# CHILD_BOARD.net
KiCad netlist of a schematic drawn in Altium Designer
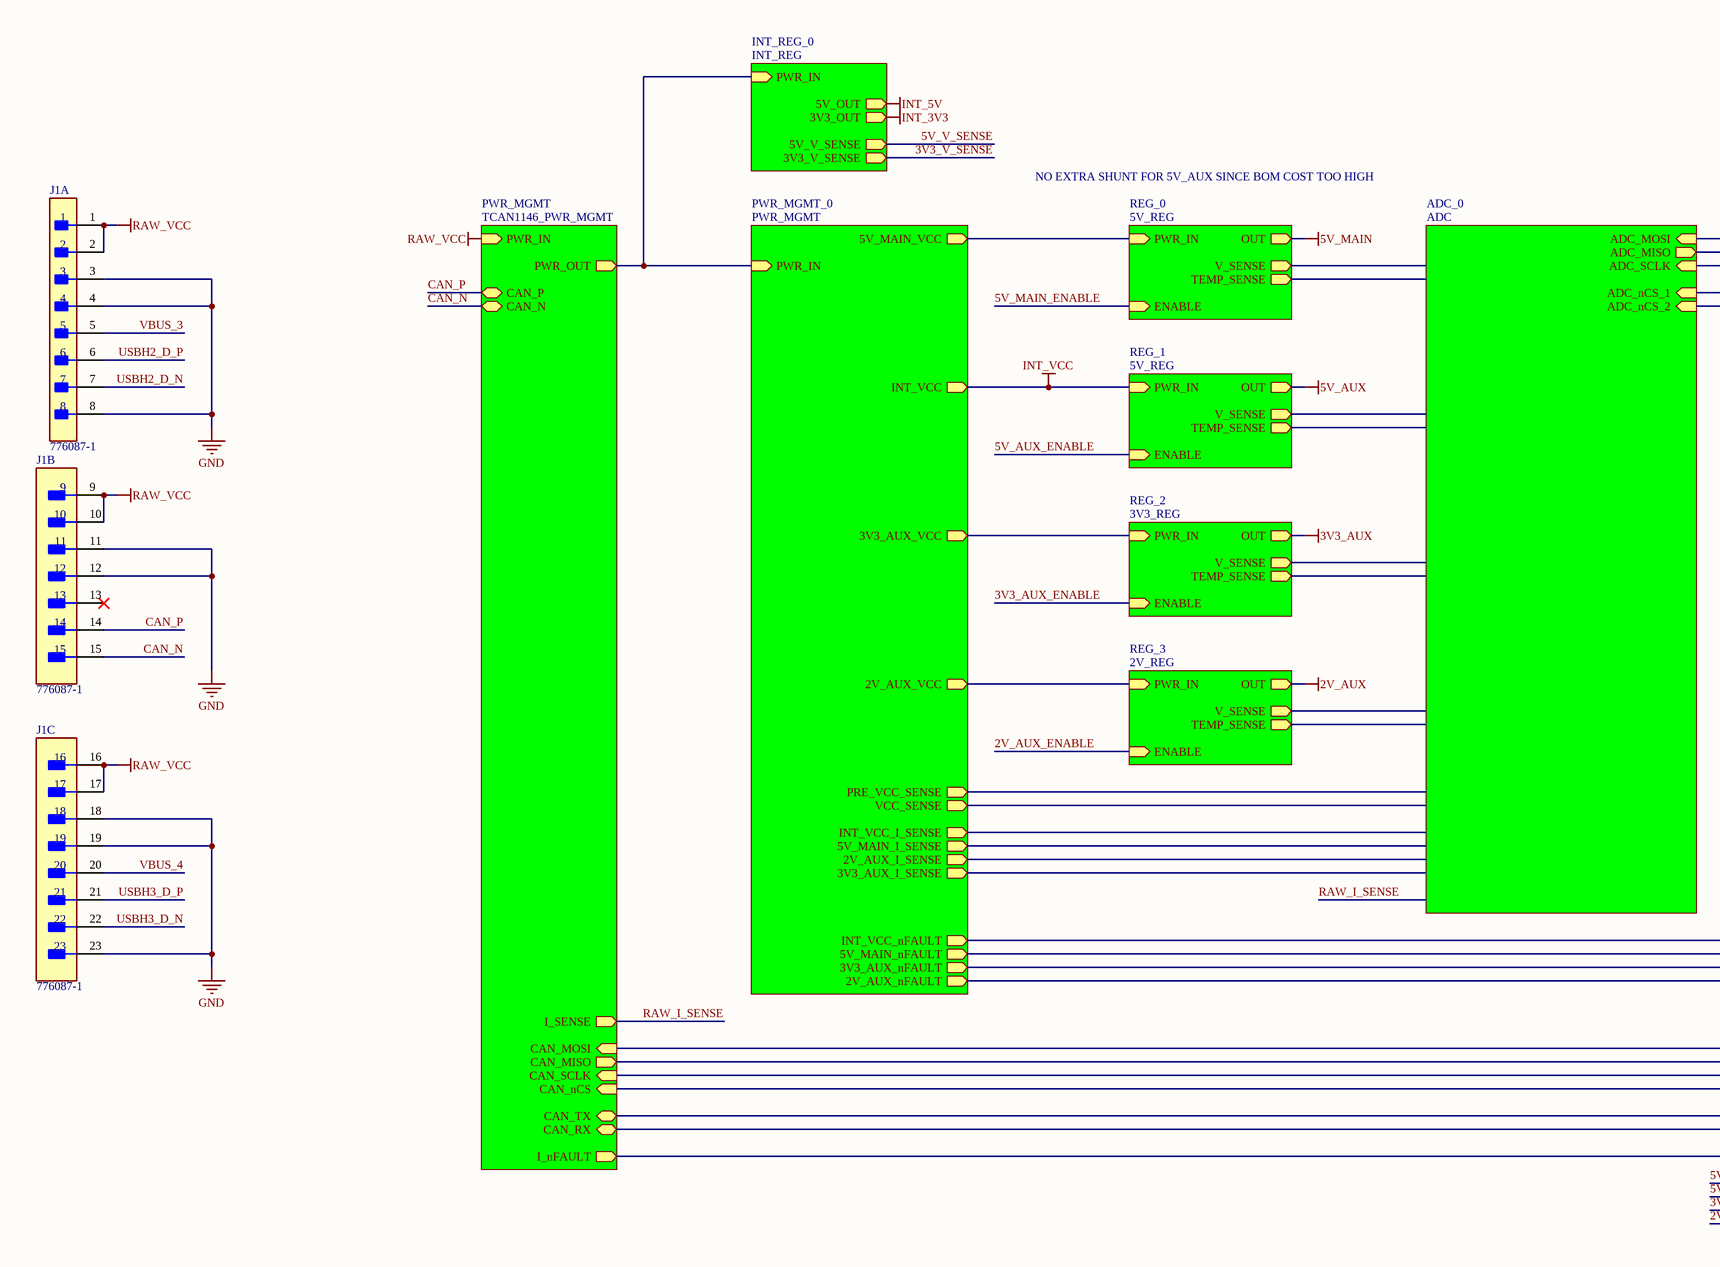
[diagram p0: CHILD_BOARD.SchDoc, left]
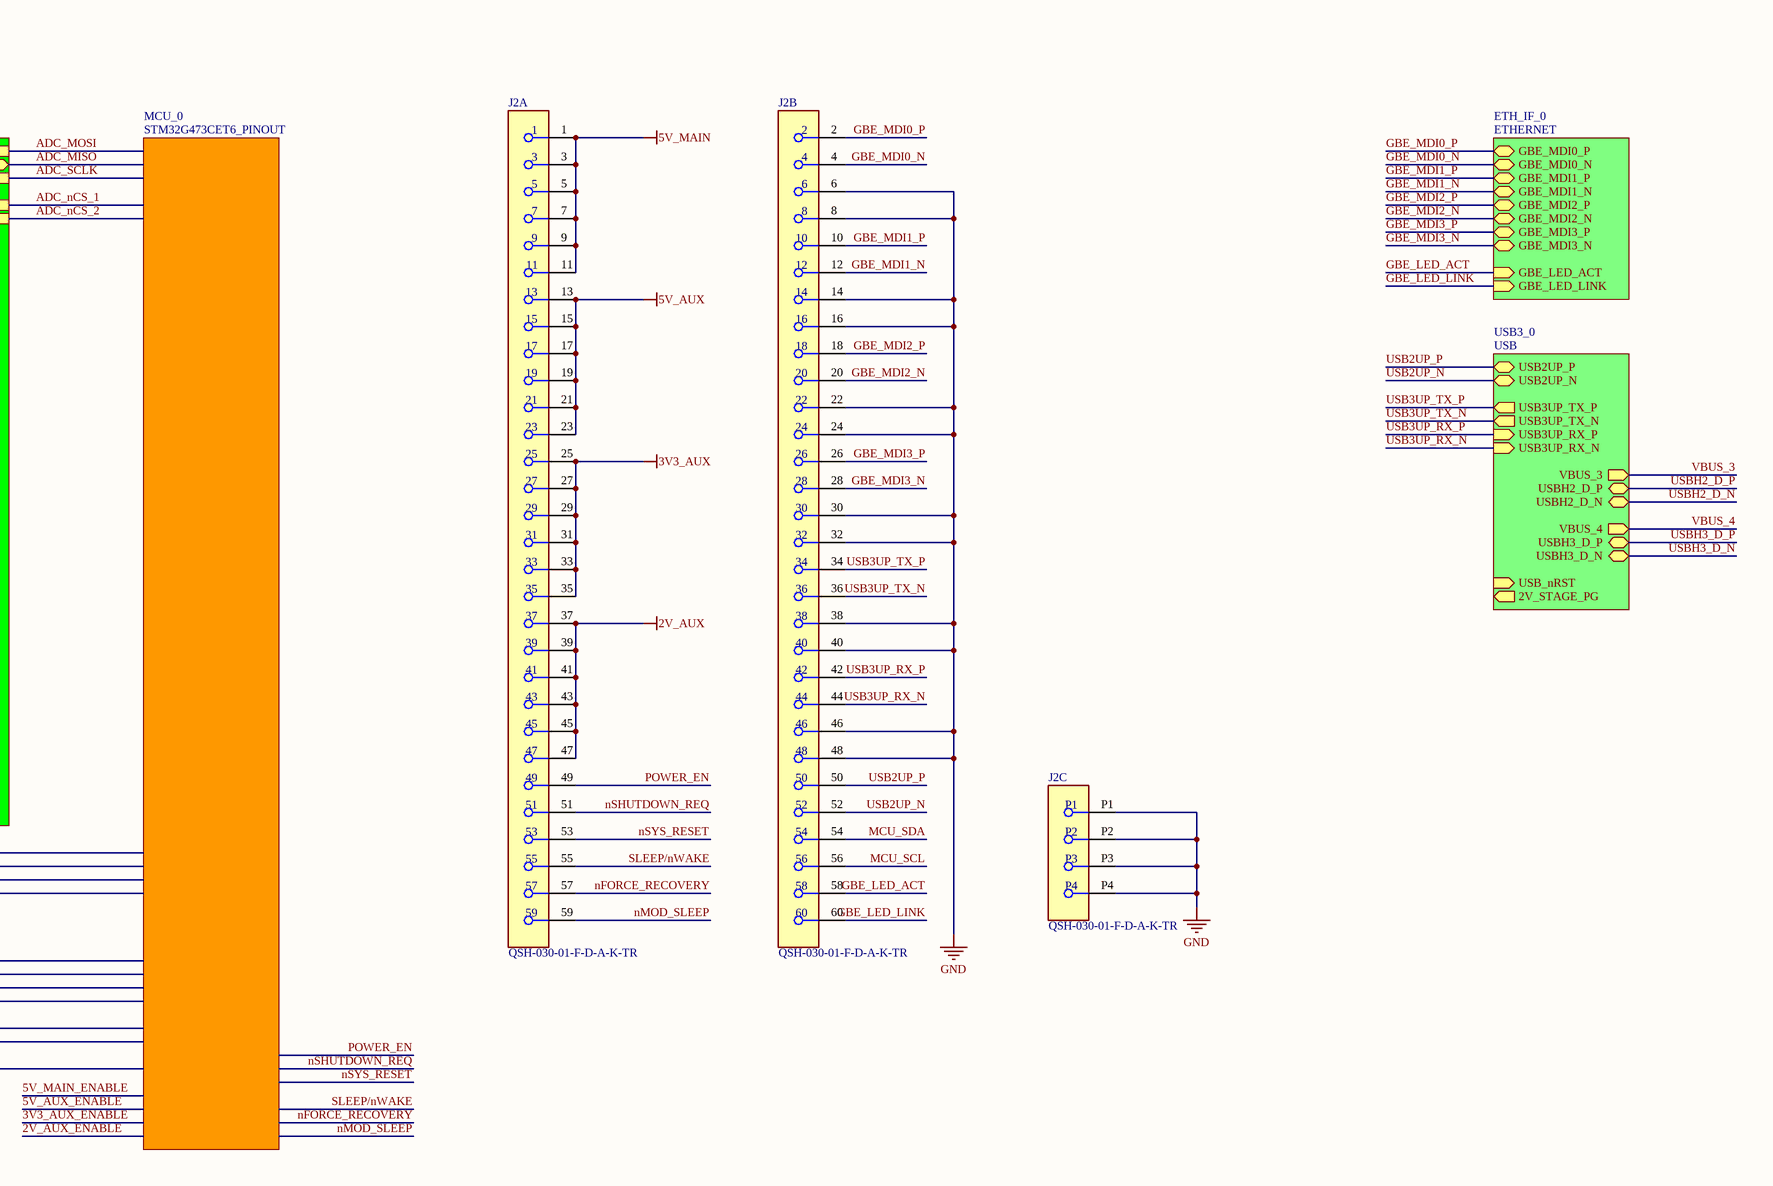
[diagram p1: CHILD_BOARD.SchDoc, right]

(export (version "E")
  (design (tool "Eeschema 10.0.6"))
  (components
    (comp (ref "J1")
      (value "776087-1")
      (footprint "FP-776087-1-MFG")
      (description "CONN HEADER R/A 23POS 4MM")
      (libsource (lib "Altium Content Vault") (part "1cdbe6524175775e54446a79a4f0ed8"))
    )
    (comp (ref "J2")
      (value "QSH-030-01-F-D-A-K-TR")
      (footprint "FP-QSH-030-01-F-D-A-K-TR-MFG")
      (description "CONN RCPT 60POS SMD GOLD")
      (libsource (lib "Altium Content Vault") (part "48abaac3d53574362e26c425c264dad"))
    )
  )
  (nets
    (net (code "24") (name "/CAN_N") (class "Default")
      (node (ref "J1") (pin "15") (pinfunction "15_15") (pintype "passive"))
    )
    (net (code "25") (name "/CAN_P") (class "Default")
      (node (ref "J1") (pin "14") (pinfunction "14_14") (pintype "passive"))
    )
    (net (code "30") (name "/GBE_LED_ACT") (class "Default")
      (node (ref "J2") (pin "58") (pinfunction "58_58") (pintype "passive"))
    )
    (net (code "31") (name "/GBE_LED_LINK") (class "Default")
      (node (ref "J2") (pin "60") (pinfunction "60_60") (pintype "passive"))
    )
    (net (code "32") (name "/GBE_MDI0_N") (class "Default")
      (node (ref "J2") (pin "4") (pinfunction "4_4") (pintype "passive"))
    )
    (net (code "33") (name "/GBE_MDI0_P") (class "Default")
      (node (ref "J2") (pin "2") (pinfunction "2_2") (pintype "passive"))
    )
    (net (code "34") (name "/GBE_MDI1_N") (class "Default")
      (node (ref "J2") (pin "12") (pinfunction "12_12") (pintype "passive"))
    )
    (net (code "35") (name "/GBE_MDI1_P") (class "Default")
      (node (ref "J2") (pin "10") (pinfunction "10_10") (pintype "passive"))
    )
    (net (code "36") (name "/GBE_MDI2_N") (class "Default")
      (node (ref "J2") (pin "20") (pinfunction "20_20") (pintype "passive"))
    )
    (net (code "37") (name "/GBE_MDI2_P") (class "Default")
      (node (ref "J2") (pin "18") (pinfunction "18_18") (pintype "passive"))
    )
    (net (code "38") (name "/GBE_MDI3_N") (class "Default")
      (node (ref "J2") (pin "28") (pinfunction "28_28") (pintype "passive"))
    )
    (net (code "39") (name "/GBE_MDI3_P") (class "Default")
      (node (ref "J2") (pin "26") (pinfunction "26_26") (pintype "passive"))
    )
    (net (code "43") (name "/MCU_SCL") (class "Default")
      (node (ref "J2") (pin "56") (pinfunction "56_56") (pintype "passive"))
    )
    (net (code "44") (name "/MCU_SDA") (class "Default")
      (node (ref "J2") (pin "54") (pinfunction "54_54") (pintype "passive"))
    )
    (net (code "45") (name "/POWER_EN") (class "Default")
      (node (ref "J2") (pin "49") (pinfunction "49_49") (pintype "passive"))
    )
    (net (code "49") (name "/SLEEP{slash}nWAKE") (class "Default")
      (node (ref "J2") (pin "55") (pinfunction "55_55") (pintype "passive"))
    )
    (net (code "54") (name "/USB2UP_N") (class "Default")
      (node (ref "J2") (pin "52") (pinfunction "52_52") (pintype "passive"))
    )
    (net (code "55") (name "/USB2UP_P") (class "Default")
      (node (ref "J2") (pin "50") (pinfunction "50_50") (pintype "passive"))
    )
    (net (code "56") (name "/USB3UP_RX_N") (class "Default")
      (node (ref "J2") (pin "44") (pinfunction "44_44") (pintype "passive"))
    )
    (net (code "57") (name "/USB3UP_RX_P") (class "Default")
      (node (ref "J2") (pin "42") (pinfunction "42_42") (pintype "passive"))
    )
    (net (code "58") (name "/USB3UP_TX_N") (class "Default")
      (node (ref "J2") (pin "36") (pinfunction "36_36") (pintype "passive"))
    )
    (net (code "59") (name "/USB3UP_TX_P") (class "Default")
      (node (ref "J2") (pin "34") (pinfunction "34_34") (pintype "passive"))
    )
    (net (code "60") (name "/USBH2_D_N") (class "Default")
      (node (ref "J1") (pin "7") (pinfunction "7_7") (pintype "passive"))
    )
    (net (code "61") (name "/USBH2_D_P") (class "Default")
      (node (ref "J1") (pin "6") (pinfunction "6_6") (pintype "passive"))
    )
    (net (code "62") (name "/USBH3_D_N") (class "Default")
      (node (ref "J1") (pin "22") (pinfunction "22_22") (pintype "passive"))
    )
    (net (code "63") (name "/USBH3_D_P") (class "Default")
      (node (ref "J1") (pin "21") (pinfunction "21_21") (pintype "passive"))
    )
    (net (code "65") (name "/VBUS_3") (class "Default")
      (node (ref "J1") (pin "5") (pinfunction "5_5") (pintype "passive"))
    )
    (net (code "66") (name "/VBUS_4") (class "Default")
      (node (ref "J1") (pin "20") (pinfunction "20_20") (pintype "passive"))
    )
    (net (code "72") (name "/nFORCE_RECOVERY") (class "Default")
      (node (ref "J2") (pin "57") (pinfunction "57_57") (pintype "passive"))
    )
    (net (code "73") (name "/nMOD_SLEEP") (class "Default")
      (node (ref "J2") (pin "59") (pinfunction "59_59") (pintype "passive"))
    )
    (net (code "74") (name "/nSHUTDOWN_REQ") (class "Default")
      (node (ref "J2") (pin "51") (pinfunction "51_51") (pintype "passive"))
    )
    (net (code "75") (name "/nSYS_RESET") (class "Default")
      (node (ref "J2") (pin "53") (pinfunction "53_53") (pintype "passive"))
    )
    (net (code "76") (name "2V_AUX") (class "Default")
      (node (ref "J2") (pin "37") (pinfunction "37_37") (pintype "passive"))
      (node (ref "J2") (pin "39") (pinfunction "39_39") (pintype "passive"))
      (node (ref "J2") (pin "41") (pinfunction "41_41") (pintype "passive"))
      (node (ref "J2") (pin "43") (pinfunction "43_43") (pintype "passive"))
      (node (ref "J2") (pin "45") (pinfunction "45_45") (pintype "passive"))
      (node (ref "J2") (pin "47") (pinfunction "47_47") (pintype "passive"))
    )
    (net (code "77") (name "3V3_AUX") (class "Default")
      (node (ref "J2") (pin "25") (pinfunction "25_25") (pintype "passive"))
      (node (ref "J2") (pin "27") (pinfunction "27_27") (pintype "passive"))
      (node (ref "J2") (pin "29") (pinfunction "29_29") (pintype "passive"))
      (node (ref "J2") (pin "31") (pinfunction "31_31") (pintype "passive"))
      (node (ref "J2") (pin "33") (pinfunction "33_33") (pintype "passive"))
      (node (ref "J2") (pin "35") (pinfunction "35_35") (pintype "passive"))
    )
    (net (code "78") (name "5V_AUX") (class "Default")
      (node (ref "J2") (pin "13") (pinfunction "13_13") (pintype "passive"))
      (node (ref "J2") (pin "15") (pinfunction "15_15") (pintype "passive"))
      (node (ref "J2") (pin "17") (pinfunction "17_17") (pintype "passive"))
      (node (ref "J2") (pin "19") (pinfunction "19_19") (pintype "passive"))
      (node (ref "J2") (pin "21") (pinfunction "21_21") (pintype "passive"))
      (node (ref "J2") (pin "23") (pinfunction "23_23") (pintype "passive"))
    )
    (net (code "79") (name "5V_MAIN") (class "Default")
      (node (ref "J2") (pin "1") (pinfunction "1_1") (pintype "passive"))
      (node (ref "J2") (pin "11") (pinfunction "11_11") (pintype "passive"))
      (node (ref "J2") (pin "3") (pinfunction "3_3") (pintype "passive"))
      (node (ref "J2") (pin "5") (pinfunction "5_5") (pintype "passive"))
      (node (ref "J2") (pin "7") (pinfunction "7_7") (pintype "passive"))
      (node (ref "J2") (pin "9") (pinfunction "9_9") (pintype "passive"))
    )
    (net (code "80") (name "GND") (class "Default")
      (node (ref "J1") (pin "11") (pinfunction "11_11") (pintype "passive"))
      (node (ref "J1") (pin "12") (pinfunction "12_12") (pintype "passive"))
      (node (ref "J1") (pin "18") (pinfunction "18_18") (pintype "passive"))
      (node (ref "J1") (pin "19") (pinfunction "19_19") (pintype "passive"))
      (node (ref "J1") (pin "23") (pinfunction "23_23") (pintype "passive"))
      (node (ref "J1") (pin "3") (pinfunction "3_3") (pintype "passive"))
      (node (ref "J1") (pin "4") (pinfunction "4_4") (pintype "passive"))
      (node (ref "J1") (pin "8") (pinfunction "8_8") (pintype "passive"))
      (node (ref "J2") (pin "14") (pinfunction "14_14") (pintype "passive"))
      (node (ref "J2") (pin "16") (pinfunction "16_16") (pintype "passive"))
      (node (ref "J2") (pin "22") (pinfunction "22_22") (pintype "passive"))
      (node (ref "J2") (pin "24") (pinfunction "24_24") (pintype "passive"))
      (node (ref "J2") (pin "30") (pinfunction "30_30") (pintype "passive"))
      (node (ref "J2") (pin "32") (pinfunction "32_32") (pintype "passive"))
      (node (ref "J2") (pin "38") (pinfunction "38_38") (pintype "passive"))
      (node (ref "J2") (pin "40") (pinfunction "40_40") (pintype "passive"))
      (node (ref "J2") (pin "46") (pinfunction "46_46") (pintype "passive"))
      (node (ref "J2") (pin "48") (pinfunction "48_48") (pintype "passive"))
      (node (ref "J2") (pin "6") (pinfunction "6_6") (pintype "passive"))
      (node (ref "J2") (pin "8") (pinfunction "8_8") (pintype "passive"))
      (node (ref "J2") (pin "P1") (pinfunction "P1_P1") (pintype "power_in"))
      (node (ref "J2") (pin "P2") (pinfunction "P2_P2") (pintype "power_in"))
      (node (ref "J2") (pin "P3") (pinfunction "P3_P3") (pintype "power_in"))
      (node (ref "J2") (pin "P4") (pinfunction "P4_P4") (pintype "power_in"))
    )
    (net (code "84") (name "RAW_VCC") (class "Default")
      (node (ref "J1") (pin "1") (pinfunction "1_1") (pintype "passive"))
      (node (ref "J1") (pin "10") (pinfunction "10_10") (pintype "passive"))
      (node (ref "J1") (pin "16") (pinfunction "16_16") (pintype "passive"))
      (node (ref "J1") (pin "17") (pinfunction "17_17") (pintype "passive"))
      (node (ref "J1") (pin "2") (pinfunction "2_2") (pintype "passive"))
      (node (ref "J1") (pin "9") (pinfunction "9_9") (pintype "passive"))
    )
    (net (code "85") (name "unconnected-(J1-Pad13)") (class "Default")
      (node (ref "J1") (pin "13") (pinfunction "13_13") (pintype "passive+no_connect"))
    )
  )
)
